# 16-DPLL_Spare_UFL.net
KiCad netlist of a schematic drawn in Altium Designer
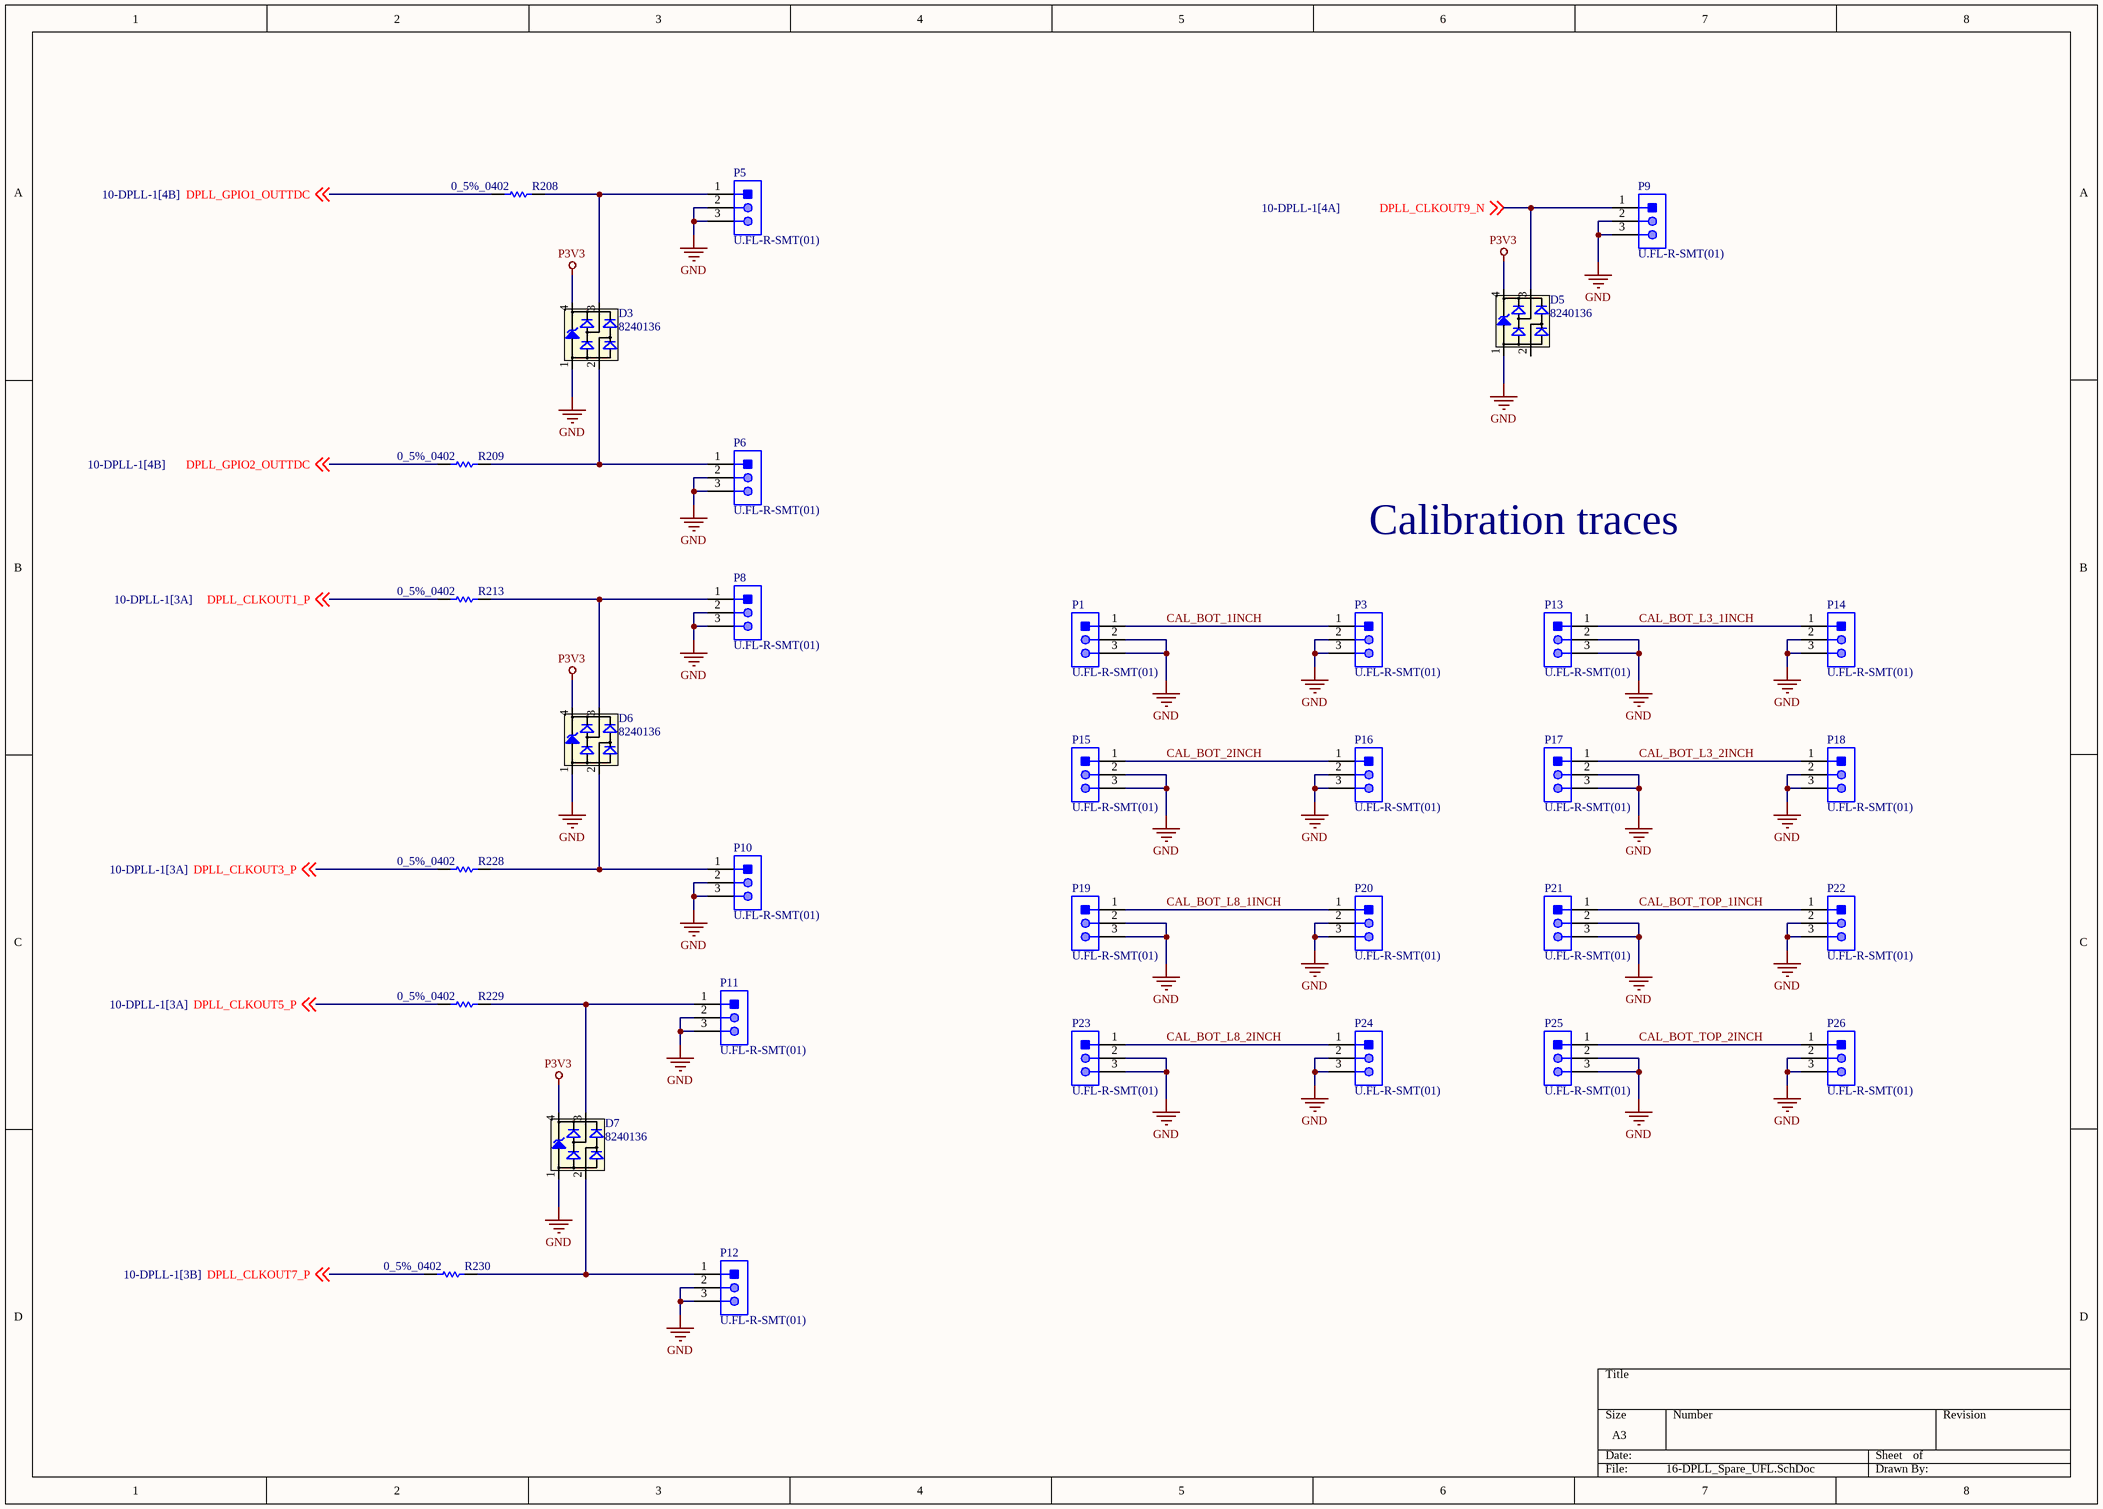
[diagram p0: 16-DPLL_Spare_UFL.SchDoc]

(export (version "E")
  (design (tool "Eeschema 10.0.6"))
  (components
    (comp (ref "D3")
      (value "8240136")
      (footprint "SOT143-4L")
      (description "TVS Diode WE-TVS-HS, VRWM=3.3V")
      (fields (field (name "MANUFACTURER") "Wuerth Elektronik"))
      (libsource (lib "Altium Content Vault") (part "WE-TVS-HS-4"))
    )
    (comp (ref "D5")
      (value "8240136")
      (footprint "SOT143-4L")
      (description "TVS Diode WE-TVS-HS, VRWM=3.3V")
      (fields (field (name "MANUFACTURER") "Wuerth Elektronik"))
      (libsource (lib "Altium Content Vault") (part "WE-TVS-HS-4"))
    )
    (comp (ref "D6")
      (value "8240136")
      (footprint "SOT143-4L")
      (description "TVS Diode WE-TVS-HS, VRWM=3.3V")
      (fields (field (name "MANUFACTURER") "Wuerth Elektronik"))
      (libsource (lib "Altium Content Vault") (part "WE-TVS-HS-4"))
    )
    (comp (ref "D7")
      (value "8240136")
      (footprint "SOT143-4L")
      (description "TVS Diode WE-TVS-HS, VRWM=3.3V")
      (fields (field (name "MANUFACTURER") "Wuerth Elektronik"))
      (libsource (lib "Altium Content Vault") (part "WE-TVS-HS-4"))
    )
    (comp (ref "P1")
      (value "U.FL-R-SMT(01)")
      (footprint "HRS-U.FL-R-SMT(10)_V")
      (description "CONN RECPT ULTRA-MINI COAX SMD")
      (fields (field (name "MANUFACTURER") "Hirose Electric") (field (name "APPROVAL CATEGORY") "UL94V-0"))
      (libsource (lib "") (part "CN-1P-M-R3_1"))
    )
    (comp (ref "P3")
      (value "U.FL-R-SMT(01)")
      (footprint "HRS-U.FL-R-SMT(10)_V")
      (description "CONN RECPT ULTRA-MINI COAX SMD")
      (fields (field (name "MANUFACTURER") "Hirose Electric") (field (name "APPROVAL CATEGORY") "UL94V-0"))
      (libsource (lib "Altium Content Vault") (part "CN-1P-M-R3"))
    )
    (comp (ref "P5")
      (value "U.FL-R-SMT(01)")
      (footprint "HRS-U.FL-R-SMT(10)_V")
      (description "CONN RECPT ULTRA-MINI COAX SMD")
      (fields (field (name "MANUFACTURER") "Hirose Electric") (field (name "APPROVAL CATEGORY") "UL94V-0"))
      (libsource (lib "Altium Content Vault") (part "CN-1P-M-R3"))
    )
    (comp (ref "P6")
      (value "U.FL-R-SMT(01)")
      (footprint "HRS-U.FL-R-SMT(10)_V")
      (description "CONN RECPT ULTRA-MINI COAX SMD")
      (fields (field (name "MANUFACTURER") "Hirose Electric") (field (name "APPROVAL CATEGORY") "UL94V-0"))
      (libsource (lib "Altium Content Vault") (part "CN-1P-M-R3"))
    )
    (comp (ref "P8")
      (value "U.FL-R-SMT(01)")
      (footprint "HRS-U.FL-R-SMT(10)_V")
      (description "CONN RECPT ULTRA-MINI COAX SMD")
      (fields (field (name "MANUFACTURER") "Hirose Electric") (field (name "APPROVAL CATEGORY") "UL94V-0"))
      (libsource (lib "Altium Content Vault") (part "CN-1P-M-R3"))
    )
    (comp (ref "P9")
      (value "U.FL-R-SMT(01)")
      (footprint "HRS-U.FL-R-SMT(10)_V")
      (description "CONN RECPT ULTRA-MINI COAX SMD")
      (fields (field (name "MANUFACTURER") "Hirose Electric") (field (name "APPROVAL CATEGORY") "UL94V-0"))
      (libsource (lib "Altium Content Vault") (part "CN-1P-M-R3"))
    )
    (comp (ref "P10")
      (value "U.FL-R-SMT(01)")
      (footprint "HRS-U.FL-R-SMT(10)_V")
      (description "CONN RECPT ULTRA-MINI COAX SMD")
      (fields (field (name "MANUFACTURER") "Hirose Electric") (field (name "APPROVAL CATEGORY") "UL94V-0"))
      (libsource (lib "Altium Content Vault") (part "CN-1P-M-R3"))
    )
    (comp (ref "P11")
      (value "U.FL-R-SMT(01)")
      (footprint "HRS-U.FL-R-SMT(10)_V")
      (description "CONN RECPT ULTRA-MINI COAX SMD")
      (fields (field (name "MANUFACTURER") "Hirose Electric") (field (name "APPROVAL CATEGORY") "UL94V-0"))
      (libsource (lib "Altium Content Vault") (part "CN-1P-M-R3"))
    )
    (comp (ref "P12")
      (value "U.FL-R-SMT(01)")
      (footprint "HRS-U.FL-R-SMT(10)_V")
      (description "CONN RECPT ULTRA-MINI COAX SMD")
      (fields (field (name "MANUFACTURER") "Hirose Electric") (field (name "APPROVAL CATEGORY") "UL94V-0"))
      (libsource (lib "Altium Content Vault") (part "CN-1P-M-R3"))
    )
    (comp (ref "P13")
      (value "U.FL-R-SMT(01)")
      (footprint "HRS-U.FL-R-SMT(10)_V")
      (description "CONN RECPT ULTRA-MINI COAX SMD")
      (fields (field (name "MANUFACTURER") "Hirose Electric") (field (name "APPROVAL CATEGORY") "UL94V-0"))
      (libsource (lib "") (part "CN-1P-M-R3_1"))
    )
    (comp (ref "P14")
      (value "U.FL-R-SMT(01)")
      (footprint "HRS-U.FL-R-SMT(10)_V")
      (description "CONN RECPT ULTRA-MINI COAX SMD")
      (fields (field (name "MANUFACTURER") "Hirose Electric") (field (name "APPROVAL CATEGORY") "UL94V-0"))
      (libsource (lib "Altium Content Vault") (part "CN-1P-M-R3"))
    )
    (comp (ref "P15")
      (value "U.FL-R-SMT(01)")
      (footprint "HRS-U.FL-R-SMT(10)_V")
      (description "CONN RECPT ULTRA-MINI COAX SMD")
      (fields (field (name "MANUFACTURER") "Hirose Electric") (field (name "APPROVAL CATEGORY") "UL94V-0"))
      (libsource (lib "") (part "CN-1P-M-R3_1"))
    )
    (comp (ref "P16")
      (value "U.FL-R-SMT(01)")
      (footprint "HRS-U.FL-R-SMT(10)_V")
      (description "CONN RECPT ULTRA-MINI COAX SMD")
      (fields (field (name "MANUFACTURER") "Hirose Electric") (field (name "APPROVAL CATEGORY") "UL94V-0"))
      (libsource (lib "Altium Content Vault") (part "CN-1P-M-R3"))
    )
    (comp (ref "P17")
      (value "U.FL-R-SMT(01)")
      (footprint "HRS-U.FL-R-SMT(10)_V")
      (description "CONN RECPT ULTRA-MINI COAX SMD")
      (fields (field (name "MANUFACTURER") "Hirose Electric") (field (name "APPROVAL CATEGORY") "UL94V-0"))
      (libsource (lib "") (part "CN-1P-M-R3_1"))
    )
    (comp (ref "P18")
      (value "U.FL-R-SMT(01)")
      (footprint "HRS-U.FL-R-SMT(10)_V")
      (description "CONN RECPT ULTRA-MINI COAX SMD")
      (fields (field (name "MANUFACTURER") "Hirose Electric") (field (name "APPROVAL CATEGORY") "UL94V-0"))
      (libsource (lib "Altium Content Vault") (part "CN-1P-M-R3"))
    )
    (comp (ref "P19")
      (value "U.FL-R-SMT(01)")
      (footprint "HRS-U.FL-R-SMT(10)_V")
      (description "CONN RECPT ULTRA-MINI COAX SMD")
      (fields (field (name "MANUFACTURER") "Hirose Electric") (field (name "APPROVAL CATEGORY") "UL94V-0"))
      (libsource (lib "") (part "CN-1P-M-R3_1"))
    )
    (comp (ref "P20")
      (value "U.FL-R-SMT(01)")
      (footprint "HRS-U.FL-R-SMT(10)_V")
      (description "CONN RECPT ULTRA-MINI COAX SMD")
      (fields (field (name "MANUFACTURER") "Hirose Electric") (field (name "APPROVAL CATEGORY") "UL94V-0"))
      (libsource (lib "Altium Content Vault") (part "CN-1P-M-R3"))
    )
    (comp (ref "P21")
      (value "U.FL-R-SMT(01)")
      (footprint "HRS-U.FL-R-SMT(10)_V")
      (description "CONN RECPT ULTRA-MINI COAX SMD")
      (fields (field (name "MANUFACTURER") "Hirose Electric") (field (name "APPROVAL CATEGORY") "UL94V-0"))
      (libsource (lib "") (part "CN-1P-M-R3_1"))
    )
    (comp (ref "P22")
      (value "U.FL-R-SMT(01)")
      (footprint "HRS-U.FL-R-SMT(10)_V")
      (description "CONN RECPT ULTRA-MINI COAX SMD")
      (fields (field (name "MANUFACTURER") "Hirose Electric") (field (name "APPROVAL CATEGORY") "UL94V-0"))
      (libsource (lib "Altium Content Vault") (part "CN-1P-M-R3"))
    )
    (comp (ref "P23")
      (value "U.FL-R-SMT(01)")
      (footprint "HRS-U.FL-R-SMT(10)_V")
      (description "CONN RECPT ULTRA-MINI COAX SMD")
      (fields (field (name "MANUFACTURER") "Hirose Electric") (field (name "APPROVAL CATEGORY") "UL94V-0"))
      (libsource (lib "") (part "CN-1P-M-R3_1"))
    )
    (comp (ref "P24")
      (value "U.FL-R-SMT(01)")
      (footprint "HRS-U.FL-R-SMT(10)_V")
      (description "CONN RECPT ULTRA-MINI COAX SMD")
      (fields (field (name "MANUFACTURER") "Hirose Electric") (field (name "APPROVAL CATEGORY") "UL94V-0"))
      (libsource (lib "Altium Content Vault") (part "CN-1P-M-R3"))
    )
    (comp (ref "P25")
      (value "U.FL-R-SMT(01)")
      (footprint "HRS-U.FL-R-SMT(10)_V")
      (description "CONN RECPT ULTRA-MINI COAX SMD")
      (fields (field (name "MANUFACTURER") "Hirose Electric") (field (name "APPROVAL CATEGORY") "UL94V-0"))
      (libsource (lib "") (part "CN-1P-M-R3_1"))
    )
    (comp (ref "P26")
      (value "U.FL-R-SMT(01)")
      (footprint "HRS-U.FL-R-SMT(10)_V")
      (description "CONN RECPT ULTRA-MINI COAX SMD")
      (fields (field (name "MANUFACTURER") "Hirose Electric") (field (name "APPROVAL CATEGORY") "UL94V-0"))
      (libsource (lib "Altium Content Vault") (part "CN-1P-M-R3"))
    )
    (comp (ref "R208")
      (value "0_5%_0402")
      (footprint "RESC1005X40X25LL10T10")
      (fields (field (name "MANUFACTURER") "KOA Speer") (field (name "PART NUMBER") "RK73Z1ETTP"))
      (libsource (lib "Altium Content Vault") (part "RES"))
    )
    (comp (ref "R209")
      (value "0_5%_0402")
      (footprint "RESC1005X40X25LL10T10")
      (fields (field (name "MANUFACTURER") "KOA Speer") (field (name "PART NUMBER") "RK73Z1ETTP"))
      (libsource (lib "Altium Content Vault") (part "RES"))
    )
    (comp (ref "R213")
      (value "0_5%_0402")
      (footprint "RESC1005X40X25LL10T10")
      (fields (field (name "MANUFACTURER") "KOA Speer") (field (name "PART NUMBER") "RK73Z1ETTP"))
      (libsource (lib "Altium Content Vault") (part "RES"))
    )
    (comp (ref "R228")
      (value "0_5%_0402")
      (footprint "RESC1005X40X25LL10T10")
      (fields (field (name "MANUFACTURER") "KOA Speer") (field (name "PART NUMBER") "RK73Z1ETTP"))
      (libsource (lib "Altium Content Vault") (part "RES"))
    )
    (comp (ref "R229")
      (value "0_5%_0402")
      (footprint "RESC1005X40X25LL10T10")
      (fields (field (name "MANUFACTURER") "KOA Speer") (field (name "PART NUMBER") "RK73Z1ETTP"))
      (libsource (lib "Altium Content Vault") (part "RES"))
    )
    (comp (ref "R230")
      (value "0_5%_0402")
      (footprint "RESC1005X40X25LL10T10")
      (fields (field (name "MANUFACTURER") "KOA Speer") (field (name "PART NUMBER") "RK73Z1ETTP"))
      (libsource (lib "Altium Content Vault") (part "RES"))
    )
  )
  (nets
    (net (code "1") (name "/CAL_BOT_1INCH") (class "Default")
      (node (ref "P1") (pin "1") (pinfunction "1_1") (pintype "passive"))
      (node (ref "P3") (pin "1") (pinfunction "1_1") (pintype "passive"))
    )
    (net (code "2") (name "/CAL_BOT_2INCH") (class "Default")
      (node (ref "P15") (pin "1") (pinfunction "1_1") (pintype "passive"))
      (node (ref "P16") (pin "1") (pinfunction "1_1") (pintype "passive"))
    )
    (net (code "3") (name "/CAL_BOT_L3_1INCH") (class "Default")
      (node (ref "P13") (pin "1") (pinfunction "1_1") (pintype "passive"))
      (node (ref "P14") (pin "1") (pinfunction "1_1") (pintype "passive"))
    )
    (net (code "4") (name "/CAL_BOT_L3_2INCH") (class "Default")
      (node (ref "P17") (pin "1") (pinfunction "1_1") (pintype "passive"))
      (node (ref "P18") (pin "1") (pinfunction "1_1") (pintype "passive"))
    )
    (net (code "5") (name "/CAL_BOT_L8_1INCH") (class "Default")
      (node (ref "P19") (pin "1") (pinfunction "1_1") (pintype "passive"))
      (node (ref "P20") (pin "1") (pinfunction "1_1") (pintype "passive"))
    )
    (net (code "6") (name "/CAL_BOT_L8_2INCH") (class "Default")
      (node (ref "P23") (pin "1") (pinfunction "1_1") (pintype "passive"))
      (node (ref "P24") (pin "1") (pinfunction "1_1") (pintype "passive"))
    )
    (net (code "7") (name "/CAL_BOT_TOP_1INCH") (class "Default")
      (node (ref "P21") (pin "1") (pinfunction "1_1") (pintype "passive"))
      (node (ref "P22") (pin "1") (pinfunction "1_1") (pintype "passive"))
    )
    (net (code "8") (name "/CAL_BOT_TOP_2INCH") (class "Default")
      (node (ref "P25") (pin "1") (pinfunction "1_1") (pintype "passive"))
      (node (ref "P26") (pin "1") (pinfunction "1_1") (pintype "passive"))
    )
    (net (code "9") (name "DPLL_CLKOUT1_P") (class "Default")
      (node (ref "R213") (pin "1") (pinfunction "1_1") (pintype "passive"))
    )
    (net (code "10") (name "DPLL_CLKOUT3_P") (class "Default")
      (node (ref "R228") (pin "1") (pinfunction "1_1") (pintype "passive"))
    )
    (net (code "11") (name "DPLL_CLKOUT5_P") (class "Default")
      (node (ref "R229") (pin "1") (pinfunction "1_1") (pintype "passive"))
    )
    (net (code "12") (name "DPLL_CLKOUT7_P") (class "Default")
      (node (ref "R230") (pin "1") (pinfunction "1_1") (pintype "passive"))
    )
    (net (code "13") (name "DPLL_CLKOUT9_N") (class "Default")
      (node (ref "D5") (pin "3") (pinfunction "I/O2_3") (pintype "passive"))
      (node (ref "P9") (pin "1") (pinfunction "1_1") (pintype "passive"))
    )
    (net (code "14") (name "DPLL_GPIO1_OUTTDC") (class "Default")
      (node (ref "R208") (pin "1") (pinfunction "1_1") (pintype "passive"))
    )
    (net (code "15") (name "DPLL_GPIO2_OUTTDC") (class "Default")
      (node (ref "R209") (pin "1") (pinfunction "1_1") (pintype "passive"))
    )
    (net (code "16") (name "GND") (class "Default")
      (node (ref "D3") (pin "1") (pinfunction "GND_1") (pintype "passive"))
      (node (ref "D5") (pin "1") (pinfunction "GND_1") (pintype "passive"))
      (node (ref "D6") (pin "1") (pinfunction "GND_1") (pintype "passive"))
      (node (ref "D7") (pin "1") (pinfunction "GND_1") (pintype "passive"))
      (node (ref "P1") (pin "2") (pinfunction "2_2") (pintype "passive"))
      (node (ref "P1") (pin "3") (pinfunction "3_3") (pintype "passive"))
      (node (ref "P10") (pin "2") (pinfunction "2_2") (pintype "passive"))
      (node (ref "P10") (pin "3") (pinfunction "3_3") (pintype "passive"))
      (node (ref "P11") (pin "2") (pinfunction "2_2") (pintype "passive"))
      (node (ref "P11") (pin "3") (pinfunction "3_3") (pintype "passive"))
      (node (ref "P12") (pin "2") (pinfunction "2_2") (pintype "passive"))
      (node (ref "P12") (pin "3") (pinfunction "3_3") (pintype "passive"))
      (node (ref "P13") (pin "2") (pinfunction "2_2") (pintype "passive"))
      (node (ref "P13") (pin "3") (pinfunction "3_3") (pintype "passive"))
      (node (ref "P14") (pin "2") (pinfunction "2_2") (pintype "passive"))
      (node (ref "P14") (pin "3") (pinfunction "3_3") (pintype "passive"))
      (node (ref "P15") (pin "2") (pinfunction "2_2") (pintype "passive"))
      (node (ref "P15") (pin "3") (pinfunction "3_3") (pintype "passive"))
      (node (ref "P16") (pin "2") (pinfunction "2_2") (pintype "passive"))
      (node (ref "P16") (pin "3") (pinfunction "3_3") (pintype "passive"))
      (node (ref "P17") (pin "2") (pinfunction "2_2") (pintype "passive"))
      (node (ref "P17") (pin "3") (pinfunction "3_3") (pintype "passive"))
      (node (ref "P18") (pin "2") (pinfunction "2_2") (pintype "passive"))
      (node (ref "P18") (pin "3") (pinfunction "3_3") (pintype "passive"))
      (node (ref "P19") (pin "2") (pinfunction "2_2") (pintype "passive"))
      (node (ref "P19") (pin "3") (pinfunction "3_3") (pintype "passive"))
      (node (ref "P20") (pin "2") (pinfunction "2_2") (pintype "passive"))
      (node (ref "P20") (pin "3") (pinfunction "3_3") (pintype "passive"))
      (node (ref "P21") (pin "2") (pinfunction "2_2") (pintype "passive"))
      (node (ref "P21") (pin "3") (pinfunction "3_3") (pintype "passive"))
      (node (ref "P22") (pin "2") (pinfunction "2_2") (pintype "passive"))
      (node (ref "P22") (pin "3") (pinfunction "3_3") (pintype "passive"))
      (node (ref "P23") (pin "2") (pinfunction "2_2") (pintype "passive"))
      (node (ref "P23") (pin "3") (pinfunction "3_3") (pintype "passive"))
      (node (ref "P24") (pin "2") (pinfunction "2_2") (pintype "passive"))
      (node (ref "P24") (pin "3") (pinfunction "3_3") (pintype "passive"))
      (node (ref "P25") (pin "2") (pinfunction "2_2") (pintype "passive"))
      (node (ref "P25") (pin "3") (pinfunction "3_3") (pintype "passive"))
      (node (ref "P26") (pin "2") (pinfunction "2_2") (pintype "passive"))
      (node (ref "P26") (pin "3") (pinfunction "3_3") (pintype "passive"))
      (node (ref "P3") (pin "2") (pinfunction "2_2") (pintype "passive"))
      (node (ref "P3") (pin "3") (pinfunction "3_3") (pintype "passive"))
      (node (ref "P5") (pin "2") (pinfunction "2_2") (pintype "passive"))
      (node (ref "P5") (pin "3") (pinfunction "3_3") (pintype "passive"))
      (node (ref "P6") (pin "2") (pinfunction "2_2") (pintype "passive"))
      (node (ref "P6") (pin "3") (pinfunction "3_3") (pintype "passive"))
      (node (ref "P8") (pin "2") (pinfunction "2_2") (pintype "passive"))
      (node (ref "P8") (pin "3") (pinfunction "3_3") (pintype "passive"))
      (node (ref "P9") (pin "2") (pinfunction "2_2") (pintype "passive"))
      (node (ref "P9") (pin "3") (pinfunction "3_3") (pintype "passive"))
    )
    (net (code "17") (name "Net-(D3-I{slash}O1)") (class "Default")
      (node (ref "D3") (pin "2") (pinfunction "I/O1_2") (pintype "passive"))
      (node (ref "P6") (pin "1") (pinfunction "1_1") (pintype "passive"))
      (node (ref "R209") (pin "2") (pinfunction "2_2") (pintype "passive"))
    )
    (net (code "18") (name "Net-(D3-I{slash}O2)") (class "Default")
      (node (ref "D3") (pin "3") (pinfunction "I/O2_3") (pintype "passive"))
      (node (ref "P5") (pin "1") (pinfunction "1_1") (pintype "passive"))
      (node (ref "R208") (pin "2") (pinfunction "2_2") (pintype "passive"))
    )
    (net (code "19") (name "Net-(D6-I{slash}O1)") (class "Default")
      (node (ref "D6") (pin "2") (pinfunction "I/O1_2") (pintype "passive"))
      (node (ref "P10") (pin "1") (pinfunction "1_1") (pintype "passive"))
      (node (ref "R228") (pin "2") (pinfunction "2_2") (pintype "passive"))
    )
    (net (code "20") (name "Net-(D6-I{slash}O2)") (class "Default")
      (node (ref "D6") (pin "3") (pinfunction "I/O2_3") (pintype "passive"))
      (node (ref "P8") (pin "1") (pinfunction "1_1") (pintype "passive"))
      (node (ref "R213") (pin "2") (pinfunction "2_2") (pintype "passive"))
    )
    (net (code "21") (name "Net-(D7-I{slash}O1)") (class "Default")
      (node (ref "D7") (pin "2") (pinfunction "I/O1_2") (pintype "passive"))
      (node (ref "P12") (pin "1") (pinfunction "1_1") (pintype "passive"))
      (node (ref "R230") (pin "2") (pinfunction "2_2") (pintype "passive"))
    )
    (net (code "22") (name "Net-(D7-I{slash}O2)") (class "Default")
      (node (ref "D7") (pin "3") (pinfunction "I/O2_3") (pintype "passive"))
      (node (ref "P11") (pin "1") (pinfunction "1_1") (pintype "passive"))
      (node (ref "R229") (pin "2") (pinfunction "2_2") (pintype "passive"))
    )
    (net (code "23") (name "P3V3") (class "Default")
      (node (ref "D3") (pin "4") (pinfunction "VDD_4") (pintype "passive"))
      (node (ref "D5") (pin "4") (pinfunction "VDD_4") (pintype "passive"))
      (node (ref "D6") (pin "4") (pinfunction "VDD_4") (pintype "passive"))
      (node (ref "D7") (pin "4") (pinfunction "VDD_4") (pintype "passive"))
    )
    (net (code "24") (name "unconnected-(D5-I{slash}O1-Pad2)") (class "Default")
      (node (ref "D5") (pin "2") (pinfunction "I/O1_2") (pintype "passive"))
    )
  )
)
